# ProPrj_BAP_PCB_Bed_Bath_2025-11-06.net
KiCad netlist of a schematic drawn in EasyEDA Pro
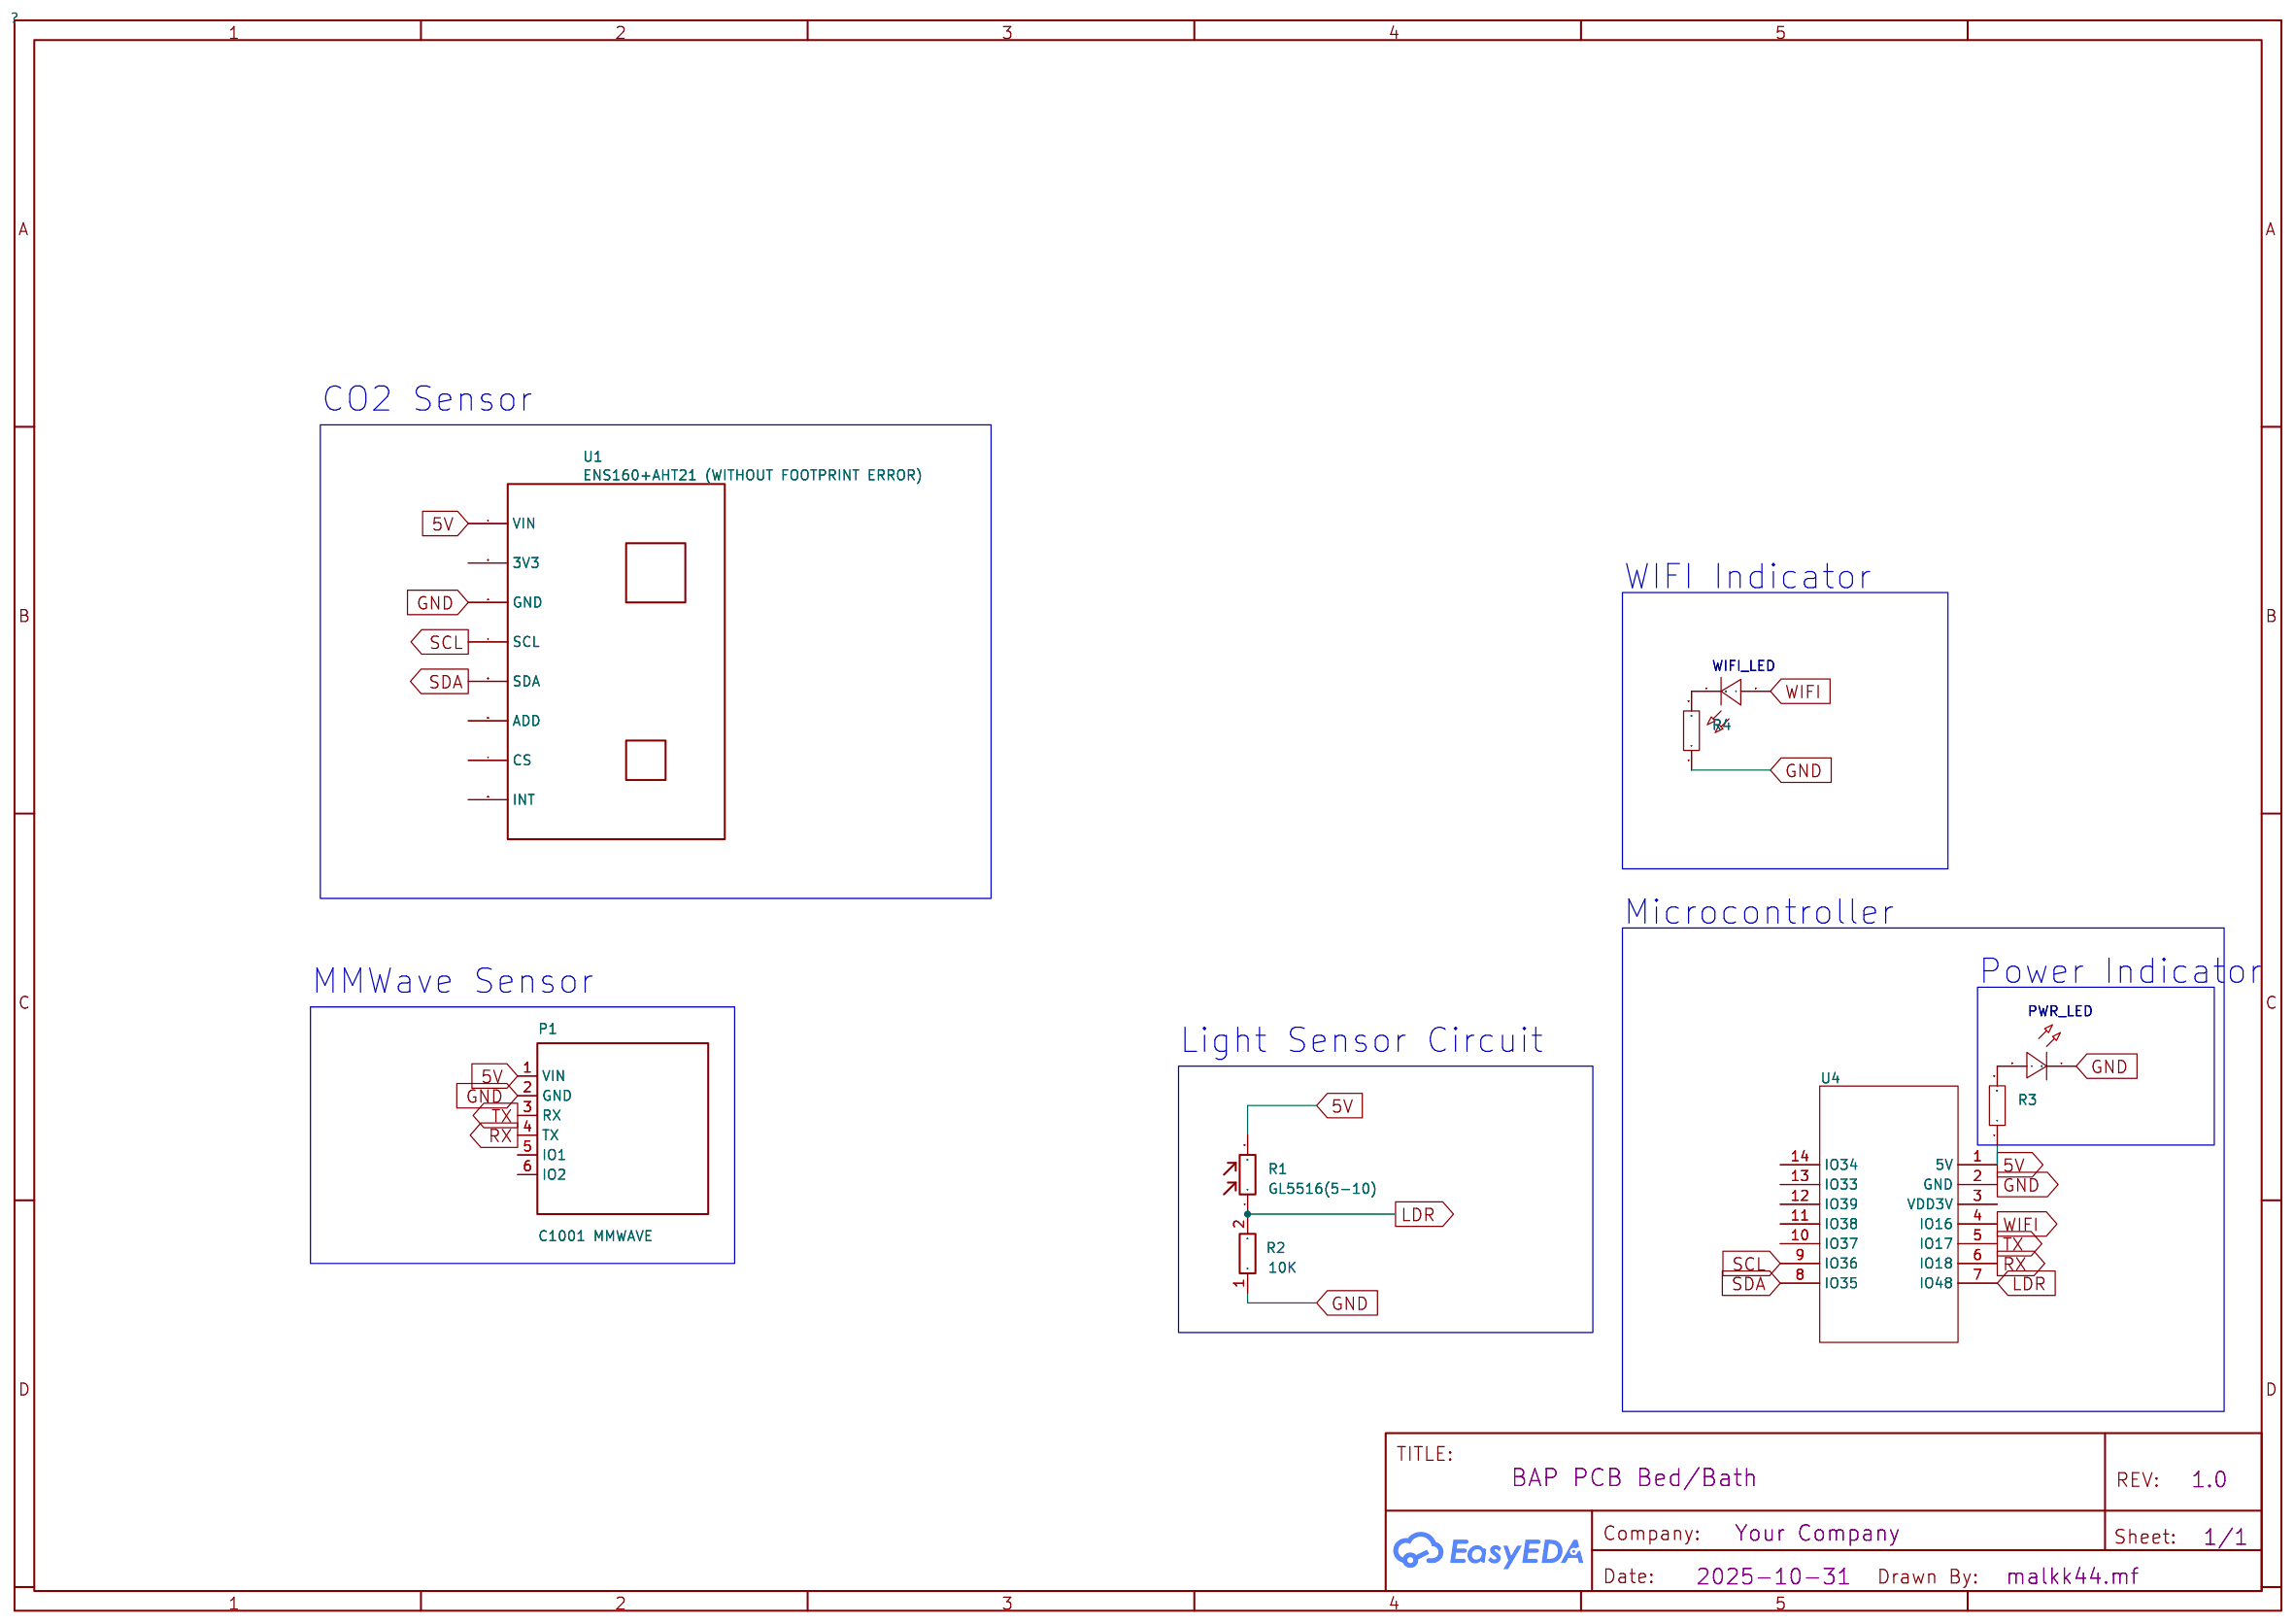
[diagram p0: schematic sheet]

(export (version "E")
  (design (tool "Eeschema 10.0.6"))
  (components
    (comp (ref "P1")
      (value "C1001 MMWAVE")
      (footprint "easyedapro:C1001 mmWave")
      (fields (field (name "Manufacturer Part") "Female header 1*6p") (field (name "Manufacturer") "BOOMELE"))
      (libsource (lib "easyedapro") (part "C1001 MMWAVE"))
    )
    (comp (ref "PWR_LED")
      (value "~")
      (footprint "easyedapro:LED_0603")
      (libsource (lib "easyedapro") (part "LED_G"))
    )
    (comp (ref "R1")
      (value "GL5516(5-10)")
      (fields (field (name "Manufacturer") "JCHL(晶创和立)"))
      (libsource (lib "easyedapro") (part "GL5516(5-10)"))
    )
    (comp (ref "R2")
      (value "10K")
      (fields
        (field (name "Manufacturer Part") "MF1/4W-330Ω±1% T")
        (field (name "Manufacturer") "CCO(千志电子)")
        (field (name "Contributor") "LCSC")
      )
      (libsource (lib "easyedapro") (part "10K"))
    )
    (comp (ref "R3")
      (value "330Ω")
      (footprint "easyedapro:RES-TH_BD2.2-L6.5-P10.50-D0.6")
      (fields (field (name "Manufacturer Part") "MFR-25FTE52-330R") (field (name "Manufacturer") "YAGEO(国巨)"))
      (libsource (lib "easyedapro") (part "MFR-25FTE52-330R"))
    )
    (comp (ref "R4")
      (value "330Ω")
      (footprint "easyedapro:RES-TH_BD2.2-L6.5-P10.50-D0.6")
      (fields (field (name "Manufacturer Part") "MFR-25FTE52-330R") (field (name "Manufacturer") "YAGEO(国巨)"))
      (libsource (lib "easyedapro") (part "MFR-25FTE52-330R"))
    )
    (comp (ref "U1")
      (value "ENS160+AHT21 (WITHOUT FOOTPRINT ERROR)")
      (fields
        (field (name "Manufacturer Part") "ENS160-AHT21 Air sensor")
        (field (name "Contributor") "vkbr")
      )
      (libsource (lib "easyedapro") (part "ENS160+AHT21 (WITHOUT FOOTPRINT ERROR)"))
    )
    (comp (ref "U4")
      (value "~")
      (footprint "easyedapro:LilyGO TQ-T Pro")
      (libsource (lib "easyedapro") (part "LilyGO TQ-T Pro"))
    )
    (comp (ref "WIFI_LED")
      (value "~")
      (footprint "easyedapro:LED_0603")
      (libsource (lib "easyedapro") (part "LED_G"))
    )
  )
  (nets
    (net (code "1") (name "5V") (class "Default")
      (node (ref "P1") (pin "1") (pinfunction "VIN_1") (pintype "unspecified"))
      (node (ref "R1") (pin "2") (pinfunction "2_2") (pintype "input"))
      (node (ref "R3") (pin "1") (pinfunction "1_1") (pintype "input"))
      (node (ref "U1") (pin "1") (pinfunction "VIN_1") (pintype "unspecified"))
      (node (ref "U4") (pin "1") (pinfunction "5V_1") (pintype "output"))
    )
    (net (code "2") (name "GND") (class "Default")
      (node (ref "P1") (pin "2") (pinfunction "GND_2") (pintype "unspecified"))
      (node (ref "PWR_LED") (pin "1") (pinfunction "C_1") (pintype "input"))
      (node (ref "R2") (pin "1") (pinfunction "1_1") (pintype "unspecified"))
      (node (ref "R4") (pin "1") (pinfunction "1_1") (pintype "input"))
      (node (ref "U1") (pin "3") (pinfunction "GND_3") (pintype "unspecified"))
      (node (ref "U4") (pin "2") (pinfunction "GND_2") (pintype "output"))
    )
    (net (code "3") (name "LDR") (class "Default")
      (node (ref "R1") (pin "1") (pinfunction "1_1") (pintype "input"))
      (node (ref "R2") (pin "2") (pinfunction "2_2") (pintype "unspecified"))
      (node (ref "U4") (pin "7") (pinfunction "IO48_7") (pintype "bidirectional"))
    )
    (net (code "4") (name "Net-(PWR_LED-A)") (class "Default")
      (node (ref "PWR_LED") (pin "2") (pinfunction "A_2") (pintype "input"))
      (node (ref "R3") (pin "2") (pinfunction "2_2") (pintype "input"))
    )
    (net (code "5") (name "Net-(WIFI_LED-C)") (class "Default")
      (node (ref "R4") (pin "2") (pinfunction "2_2") (pintype "input"))
      (node (ref "WIFI_LED") (pin "1") (pinfunction "C_1") (pintype "input"))
    )
    (net (code "6") (name "RX") (class "Default")
      (node (ref "P1") (pin "4") (pinfunction "TX_4") (pintype "unspecified"))
      (node (ref "U4") (pin "6") (pinfunction "IO18_6") (pintype "bidirectional"))
    )
    (net (code "7") (name "SCL") (class "Default")
      (node (ref "U1") (pin "4") (pinfunction "SCL_4") (pintype "unspecified"))
      (node (ref "U4") (pin "9") (pinfunction "IO36_9") (pintype "bidirectional"))
    )
    (net (code "8") (name "SDA") (class "Default")
      (node (ref "U1") (pin "5") (pinfunction "SDA_5") (pintype "unspecified"))
      (node (ref "U4") (pin "8") (pinfunction "IO35_8") (pintype "bidirectional"))
    )
    (net (code "9") (name "TX") (class "Default")
      (node (ref "P1") (pin "3") (pinfunction "RX_3") (pintype "unspecified"))
      (node (ref "U4") (pin "5") (pinfunction "IO17_5") (pintype "bidirectional"))
    )
    (net (code "10") (name "WIFI") (class "Default")
      (node (ref "U4") (pin "4") (pinfunction "IO16_4") (pintype "bidirectional"))
      (node (ref "WIFI_LED") (pin "2") (pinfunction "A_2") (pintype "input"))
    )
    (net (code "11") (name "unconnected-(P1-IO1-Pad5)") (class "Default")
      (node (ref "P1") (pin "5") (pinfunction "IO1_5") (pintype "unspecified"))
    )
    (net (code "12") (name "unconnected-(P1-IO2-Pad6)") (class "Default")
      (node (ref "P1") (pin "6") (pinfunction "IO2_6") (pintype "unspecified"))
    )
    (net (code "13") (name "unconnected-(U1-3V3-Pad2)") (class "Default")
      (node (ref "U1") (pin "2") (pinfunction "3V3_2") (pintype "unspecified"))
    )
    (net (code "14") (name "unconnected-(U1-ADD-Pad6)") (class "Default")
      (node (ref "U1") (pin "6") (pinfunction "ADD_6") (pintype "unspecified"))
    )
    (net (code "15") (name "unconnected-(U1-CS-Pad7)") (class "Default")
      (node (ref "U1") (pin "7") (pinfunction "CS_7") (pintype "unspecified"))
    )
    (net (code "16") (name "unconnected-(U1-INT-Pad8)") (class "Default")
      (node (ref "U1") (pin "8") (pinfunction "INT_8") (pintype "unspecified"))
    )
    (net (code "17") (name "unconnected-(U4-IO33-Pad13)") (class "Default")
      (node (ref "U4") (pin "13") (pinfunction "IO33_13") (pintype "bidirectional"))
    )
    (net (code "18") (name "unconnected-(U4-IO34-Pad14)") (class "Default")
      (node (ref "U4") (pin "14") (pinfunction "IO34_14") (pintype "bidirectional"))
    )
    (net (code "19") (name "unconnected-(U4-IO37-Pad10)") (class "Default")
      (node (ref "U4") (pin "10") (pinfunction "IO37_10") (pintype "bidirectional"))
    )
    (net (code "20") (name "unconnected-(U4-IO38-Pad11)") (class "Default")
      (node (ref "U4") (pin "11") (pinfunction "IO38_11") (pintype "bidirectional"))
    )
    (net (code "21") (name "unconnected-(U4-IO39-Pad12)") (class "Default")
      (node (ref "U4") (pin "12") (pinfunction "IO39_12") (pintype "bidirectional"))
    )
    (net (code "22") (name "unconnected-(U4-VDD3V-Pad3)") (class "Default")
      (node (ref "U4") (pin "3") (pinfunction "VDD3V_3") (pintype "output"))
    )
  )
)
